# rev02_1.net
KiCad netlist of a schematic drawn in Altium Designer
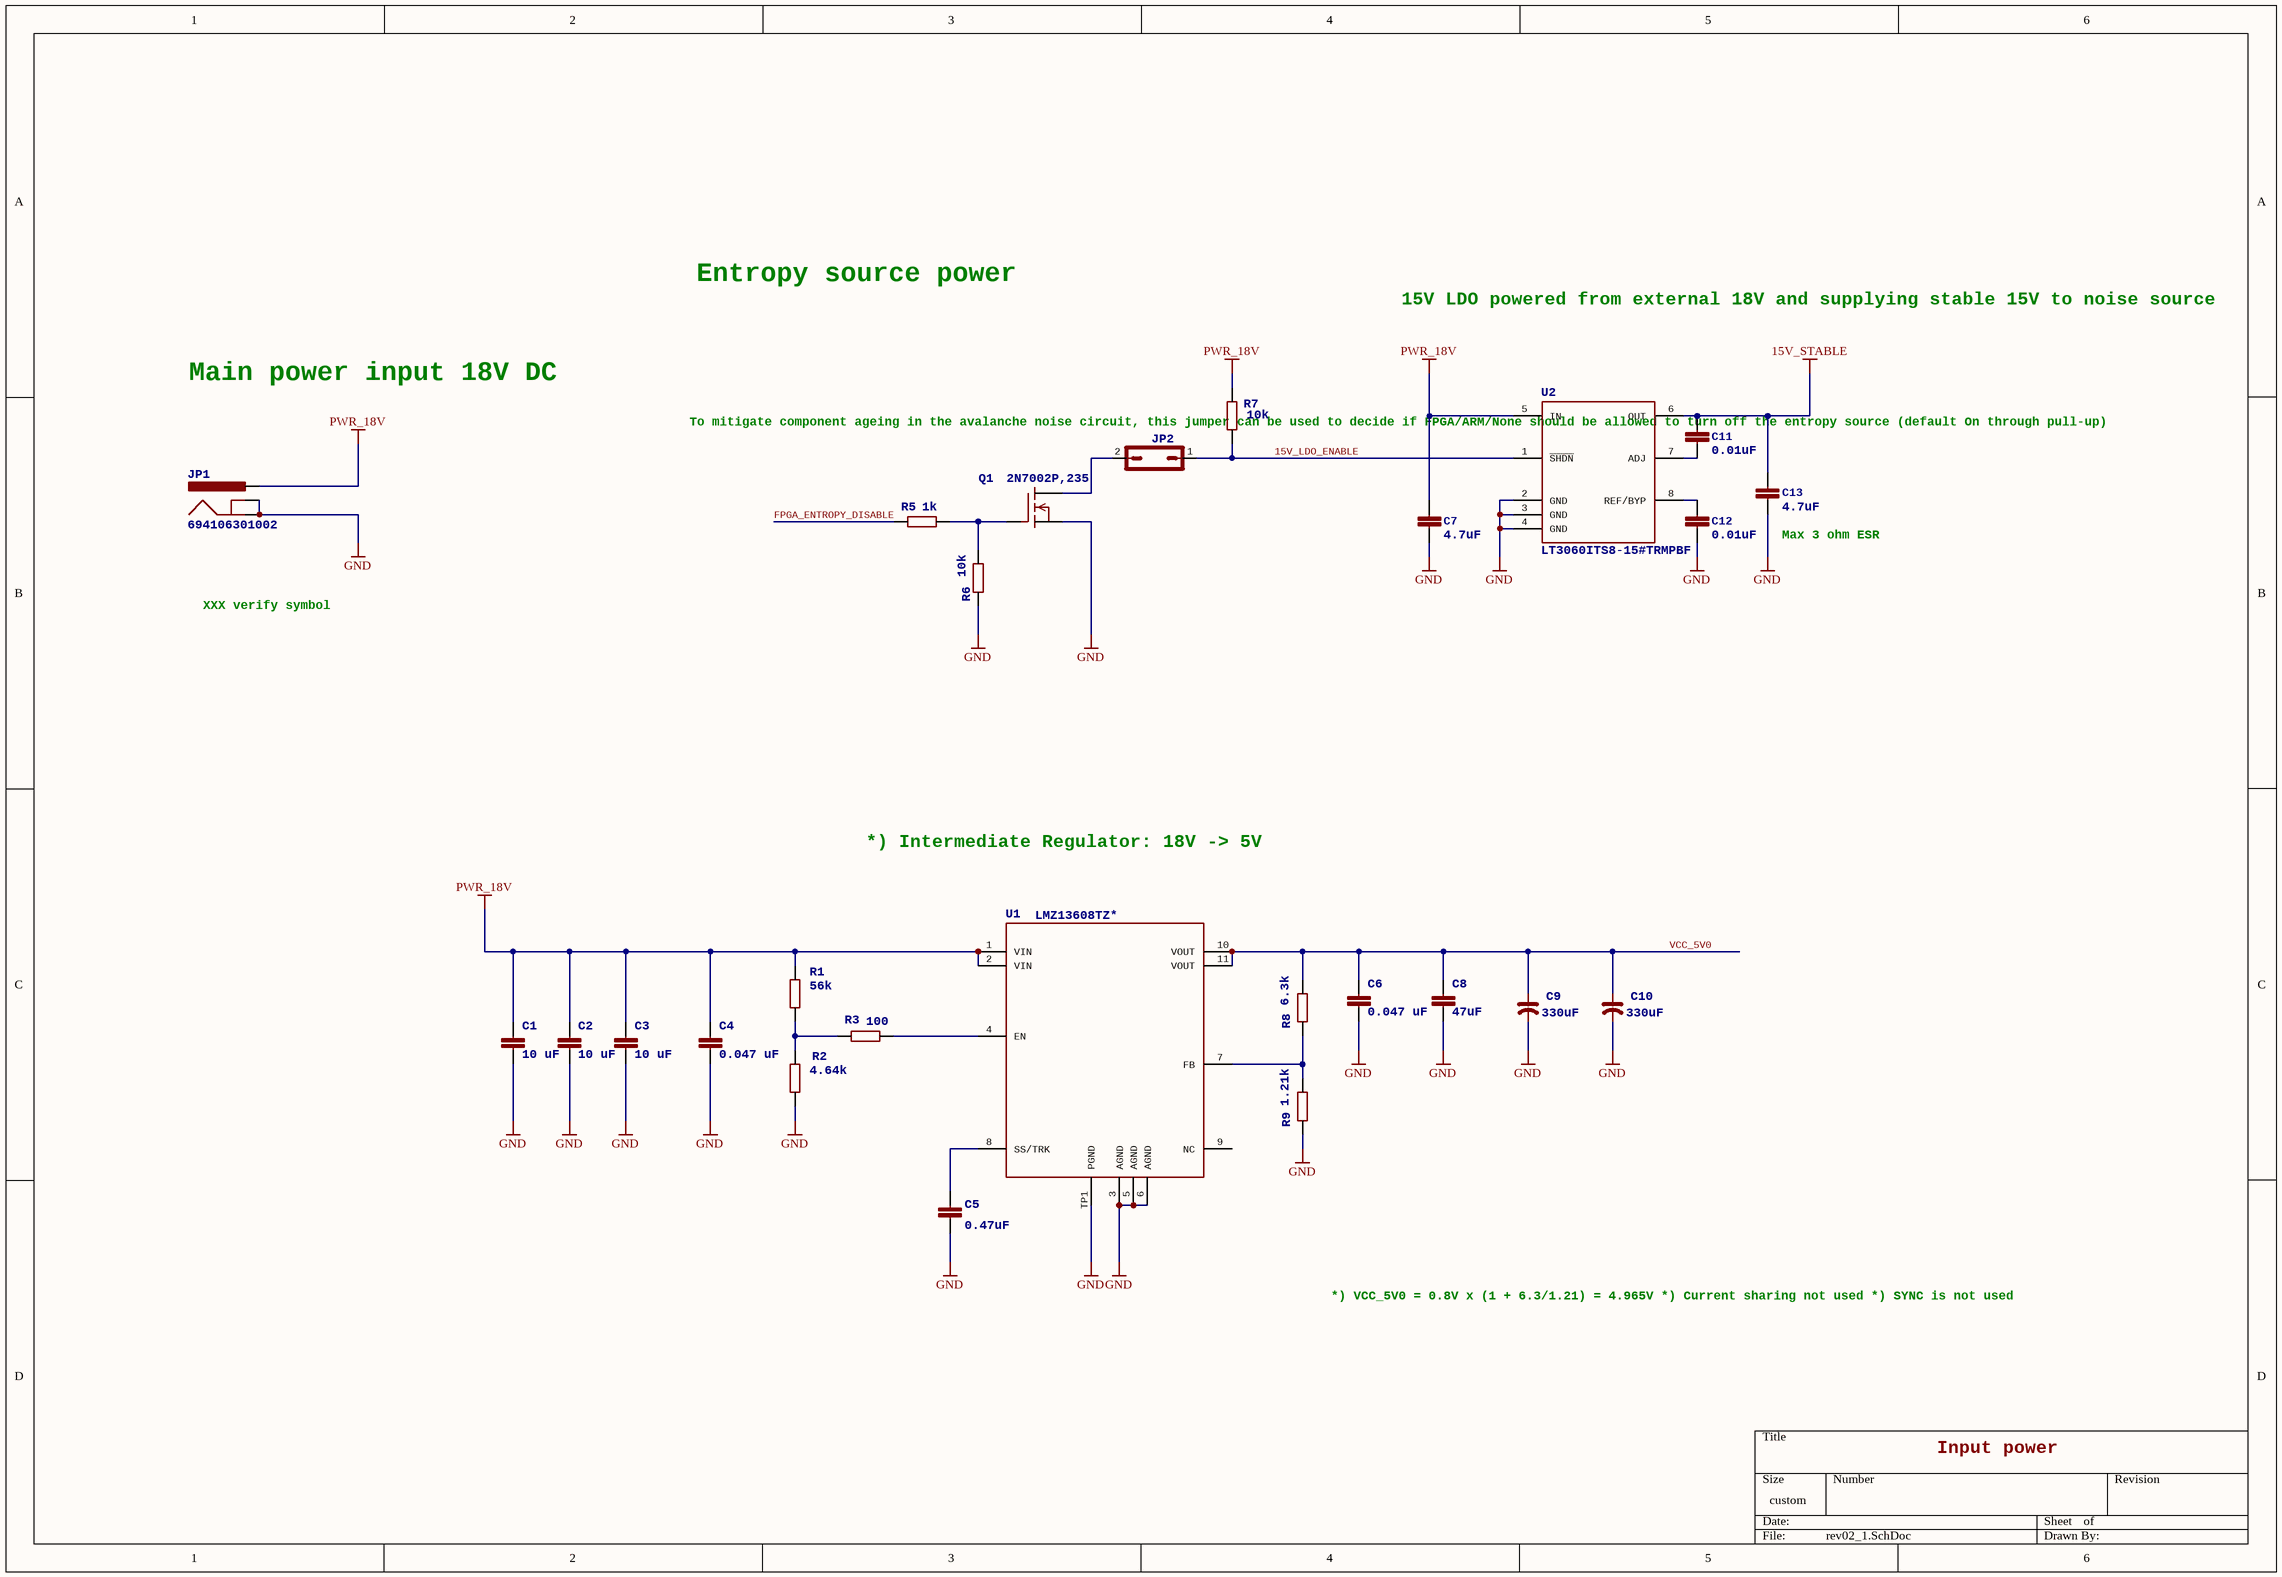
[diagram p0: rev02_1.SchDoc]

(export (version "E")
  (design (tool "Eeschema 10.0.6"))
  (components
    (comp (ref "C1")
      (value "10 uF")
      (footprint "C_1210")
      (description "1210 CAPACITOR")
      (fields (field (name "TOLERANCE") "10%") (field (name ">NAME") "C1"))
      (libsource (lib "resistor") (part "C-EUC1210"))
    )
    (comp (ref "C2")
      (value "10 uF")
      (footprint "C_1210")
      (description "1210 CAPACITOR")
      (fields (field (name "TOLERANCE") "10%") (field (name ">NAME") "C2"))
      (libsource (lib "resistor") (part "C-EUC1210"))
    )
    (comp (ref "C3")
      (value "10 uF")
      (footprint "C_1210")
      (description "1210 CAPACITOR")
      (fields (field (name "TOLERANCE") "10%") (field (name ">NAME") "C3"))
      (libsource (lib "resistor") (part "C-EUC1210"))
    )
    (comp (ref "C4")
      (value "0.047 uF")
      (footprint "C_0402")
      (description "0402 CAPACITOR")
      (fields (field (name "TOLERANCE") "10%") (field (name ">NAME") "C4"))
      (libsource (lib "resistor") (part "C-EUC0402"))
    )
    (comp (ref "C5")
      (value "0.47uF")
      (footprint "C_0402")
      (description "0402 CAPACITOR")
      (fields (field (name "TOLERANCE") "10%") (field (name "Comment") "GRM155R61A474KE15D"))
      (libsource (lib "resistor") (part "C-EUC0402"))
    )
    (comp (ref "C6")
      (value "0.047 uF")
      (footprint "C_0402")
      (description "0402 CAPACITOR")
      (fields (field (name "TOLERANCE") "10%") (field (name ">NAME") "C6"))
      (libsource (lib "resistor") (part "C-EUC0402"))
    )
    (comp (ref "C7")
      (value "4.7uF")
      (footprint "C_0805")
      (description "0805 CAPACITOR X7R 25V")
      (fields (field (name "Comment") "TMK212AB7475KG-T"))
      (libsource (lib "resistor") (part "C-EUC0603"))
    )
    (comp (ref "C8")
      (value "47uF")
      (footprint "C_1210")
      (description "1210 CAPACITOR X5R 6.3V")
      (fields
        (field (name "TOLERANCE") "20%")
        (field (name ">NAME") "C8")
        (field (name "Comment") "GRM32ER70J476ME20L")
      )
      (libsource (lib "resistor") (part "C-EUC1210"))
    )
    (comp (ref "C9")
      (value "330uF")
      (footprint "C_D")
      (description "Kemet Tantalum Capacitor")
      (fields (field (name "Comment") "T520D337M006ATE015"))
      (libsource (lib "rev02_1") (part "CP_E-035X080"))
    )
    (comp (ref "C10")
      (value "330uF")
      (footprint "C_D")
      (description "Kemet Tantalum Capacitor")
      (fields (field (name "Comment") "T520D337M006ATE015"))
      (libsource (lib "rev02_1") (part "CP_E-035X080"))
    )
    (comp (ref "C11")
      (value "0.01uF")
      (footprint "C_0402")
      (description "0402 CAPACITOR")
      (libsource (lib "rcl") (part "C-EUC0402"))
    )
    (comp (ref "C12")
      (value "0.01uF")
      (footprint "C_0402")
      (description "0402 CAPACITOR")
      (libsource (lib "rcl") (part "C-EUC0402"))
    )
    (comp (ref "C13")
      (value "4.7uF")
      (footprint "C_0805")
      (description "0805 CAPACITOR X7R 25V")
      (fields (field (name "Comment") "TMK212AB7475KG-T"))
      (libsource (lib "resistor") (part "C-EUC0603"))
    )
    (comp (ref "JP1")
      (value "694106301002")
      (footprint "694106301002")
      (description "Wurth Power Connector 5.5x2.1mm Barrel")
      (libsource (lib "rev02_1") (part "POWER_JACKSMD"))
    )
    (comp (ref "JP2")
      (value "61300211121")
      (footprint "PLS-2")
      (description "Wurth 2pins connector (for jumper)")
      (fields (field (name ">NAME") "JP2"))
      (libsource (lib "jumper") (part "JP1Q"))
    )
    (comp (ref "Q1")
      (value "2N7002P,235")
      (footprint "SOT-23")
      (description "OnSemi FET")
      (fields (field (name ">NAME") "Q1"))
      (libsource (lib "transistors_gaui") (part "2N7002"))
    )
    (comp (ref "R1")
      (value "56k")
      (footprint "R_0402")
      (description "0402 Resistor 1%")
      (libsource (lib "resistor") (part "R-EU_R0402"))
    )
    (comp (ref "R2")
      (value "4.64k")
      (footprint "R_0402")
      (description "0402 Resistor 1%")
      (libsource (lib "resistor") (part "R-EU_R0402"))
    )
    (comp (ref "R3")
      (value "100")
      (footprint "R_0402")
      (description "0402 Resistor 5%")
      (fields (field (name "TOLERANCE") "5%") (field (name ">NAME") "R3"))
      (libsource (lib "resistor") (part "R-EU_R0402"))
    )
    (comp (ref "R5")
      (value "1k")
      (footprint "R_0402")
      (description "0402 Resistor 5%")
      (libsource (lib "resistor") (part "R-EU_R0402"))
    )
    (comp (ref "R6")
      (value "10k")
      (footprint "R_0402")
      (description "0402 Resistor 5%")
      (fields (field (name "TOLERANCE") "5%") (field (name ">NAME") "R6"))
      (libsource (lib "resistor") (part "R-EU_R0402"))
    )
    (comp (ref "R7")
      (value "10k")
      (footprint "R_0402")
      (description "0402 Resistor 5%")
      (fields (field (name "TOLERANCE") "5%") (field (name ">NAME") "R7"))
      (libsource (lib "resistor") (part "R-EU_R0402"))
    )
    (comp (ref "R8")
      (value "6.3k")
      (footprint "R_0402")
      (description "0402 Resistor 1%")
      (libsource (lib "resistor") (part "R-EU_R0402"))
    )
    (comp (ref "R9")
      (value "1.21k")
      (footprint "R_0402")
      (description "0402 Resistor 1%")
      (libsource (lib "resistor") (part "R-EU_R0402"))
    )
    (comp (ref "U1")
      (value "LMZ13608TZ*")
      (footprint "NDY")
      (description "8-A SIMPLE SWITCHER® Power Module With 36-V Maximum Input Voltage")
      (fields (field (name "MPN") "LMZ13608TZ/NOPB"))
      (libsource (lib "rev02_1") (part "LMZ13608"))
    )
    (comp (ref "U2")
      (value "LT3060ITS8-15#TRMPBF")
      (footprint "TSOT-8-23")
      (description "Micropower, Low Noise, 100mA LDO, Linear Regulator")
      (libsource (lib "rev02_1") (part "LT3060ITS8-15"))
    )
  )
  (nets
    (net (code "1") (name "/15V_LDO_ENABLE") (class "Default")
      (node (ref "JP2") (pin "1") (pinfunction "1_1") (pintype "passive"))
      (node (ref "R7") (pin "2") (pinfunction "2_2") (pintype "passive"))
      (node (ref "U2") (pin "1") (pinfunction "~{SHDN}_1") (pintype "passive"))
    )
    (net (code "2") (name "/FPGA_ENTROPY_DISABLE") (class "Default")
      (node (ref "R5") (pin "1") (pinfunction "1_1") (pintype "passive"))
    )
    (net (code "3") (name "/VCC_5V0") (class "Default")
      (node (ref "C10") (pin "1") (pinfunction "+_1") (pintype "passive"))
      (node (ref "C6") (pin "1") (pinfunction "1_1") (pintype "passive"))
      (node (ref "C8") (pin "1") (pinfunction "1_1") (pintype "passive"))
      (node (ref "C9") (pin "1") (pinfunction "+_1") (pintype "passive"))
      (node (ref "R8") (pin "2") (pinfunction "2_2") (pintype "passive"))
      (node (ref "U1") (pin "10") (pinfunction "VOUT_10") (pintype "power_in"))
      (node (ref "U1") (pin "11") (pinfunction "VOUT_11") (pintype "power_in"))
    )
    (net (code "4") (name "15V_STABLE") (class "Default")
      (node (ref "C11") (pin "2") (pinfunction "2_2") (pintype "passive"))
      (node (ref "C13") (pin "1") (pinfunction "1_1") (pintype "passive"))
      (node (ref "U2") (pin "6") (pinfunction "OUT_6") (pintype "power_in"))
    )
    (net (code "5") (name "GND") (class "Default")
      (node (ref "C1") (pin "2") (pinfunction "2_2") (pintype "passive"))
      (node (ref "C10") (pin "2") (pinfunction "-_2") (pintype "passive"))
      (node (ref "C12") (pin "1") (pinfunction "1_1") (pintype "passive"))
      (node (ref "C13") (pin "2") (pinfunction "2_2") (pintype "passive"))
      (node (ref "C2") (pin "2") (pinfunction "2_2") (pintype "passive"))
      (node (ref "C3") (pin "2") (pinfunction "2_2") (pintype "passive"))
      (node (ref "C4") (pin "2") (pinfunction "2_2") (pintype "passive"))
      (node (ref "C5") (pin "2") (pinfunction "2_2") (pintype "passive"))
      (node (ref "C6") (pin "2") (pinfunction "2_2") (pintype "passive"))
      (node (ref "C7") (pin "2") (pinfunction "2_2") (pintype "passive"))
      (node (ref "C8") (pin "2") (pinfunction "2_2") (pintype "passive"))
      (node (ref "C9") (pin "2") (pinfunction "-_2") (pintype "passive"))
      (node (ref "JP1") (pin "2") (pinfunction "GND_2") (pintype "passive"))
      (node (ref "JP1") (pin "3") (pinfunction "GNDBREAK_3") (pintype "passive"))
      (node (ref "Q1") (pin "2") (pinfunction "S_2") (pintype "passive"))
      (node (ref "R2") (pin "1") (pinfunction "1_1") (pintype "passive"))
      (node (ref "R6") (pin "2") (pinfunction "2_2") (pintype "passive"))
      (node (ref "R9") (pin "1") (pinfunction "1_1") (pintype "passive"))
      (node (ref "U1") (pin "3") (pinfunction "AGND_3") (pintype "power_in"))
      (node (ref "U1") (pin "5") (pinfunction "AGND_5") (pintype "power_in"))
      (node (ref "U1") (pin "6") (pinfunction "AGND_6") (pintype "power_in"))
      (node (ref "U1") (pin "TP1") (pinfunction "PGND_TP1") (pintype "power_in"))
      (node (ref "U2") (pin "2") (pinfunction "GND_2") (pintype "power_in"))
      (node (ref "U2") (pin "3") (pinfunction "GND_3") (pintype "power_in"))
      (node (ref "U2") (pin "4") (pinfunction "GND_4") (pintype "power_in"))
    )
    (net (code "6") (name "Net-(Q1-D)") (class "Default")
      (node (ref "JP2") (pin "2") (pinfunction "2_2") (pintype "passive"))
      (node (ref "Q1") (pin "3") (pinfunction "D_3") (pintype "passive"))
    )
    (net (code "7") (name "Net-(Q1-G)") (class "Default")
      (node (ref "Q1") (pin "1") (pinfunction "G_1") (pintype "passive"))
      (node (ref "R5") (pin "2") (pinfunction "2_2") (pintype "passive"))
      (node (ref "R6") (pin "1") (pinfunction "1_1") (pintype "passive"))
    )
    (net (code "8") (name "Net-(R1-Pad1)") (class "Default")
      (node (ref "R1") (pin "1") (pinfunction "1_1") (pintype "passive"))
      (node (ref "R2") (pin "2") (pinfunction "2_2") (pintype "passive"))
      (node (ref "R3") (pin "1") (pinfunction "1_1") (pintype "passive"))
    )
    (net (code "9") (name "Net-(U1-EN)") (class "Default")
      (node (ref "R3") (pin "2") (pinfunction "2_2") (pintype "passive"))
      (node (ref "U1") (pin "4") (pinfunction "EN_4") (pintype "passive"))
    )
    (net (code "10") (name "Net-(U1-FB)") (class "Default")
      (node (ref "R8") (pin "1") (pinfunction "1_1") (pintype "passive"))
      (node (ref "R9") (pin "2") (pinfunction "2_2") (pintype "passive"))
      (node (ref "U1") (pin "7") (pinfunction "FB_7") (pintype "passive"))
    )
    (net (code "11") (name "Net-(U1-SS{slash}TRK)") (class "Default")
      (node (ref "C5") (pin "1") (pinfunction "1_1") (pintype "passive"))
      (node (ref "U1") (pin "8") (pinfunction "SS/TRK_8") (pintype "passive"))
    )
    (net (code "12") (name "Net-(U2-ADJ)") (class "Default")
      (node (ref "C11") (pin "1") (pinfunction "1_1") (pintype "passive"))
      (node (ref "U2") (pin "7") (pinfunction "ADJ_7") (pintype "passive"))
    )
    (net (code "13") (name "Net-(U2-REF{slash}BYP)") (class "Default")
      (node (ref "C12") (pin "2") (pinfunction "2_2") (pintype "passive"))
      (node (ref "U2") (pin "8") (pinfunction "REF/BYP_8") (pintype "passive"))
    )
    (net (code "14") (name "PWR_18V") (class "Default")
      (node (ref "C1") (pin "1") (pinfunction "1_1") (pintype "passive"))
      (node (ref "C2") (pin "1") (pinfunction "1_1") (pintype "passive"))
      (node (ref "C3") (pin "1") (pinfunction "1_1") (pintype "passive"))
      (node (ref "C4") (pin "1") (pinfunction "1_1") (pintype "passive"))
      (node (ref "C7") (pin "1") (pinfunction "1_1") (pintype "passive"))
      (node (ref "JP1") (pin "1") (pinfunction "PWR_1") (pintype "passive"))
      (node (ref "R1") (pin "2") (pinfunction "2_2") (pintype "passive"))
      (node (ref "R7") (pin "1") (pinfunction "1_1") (pintype "passive"))
      (node (ref "U1") (pin "1") (pinfunction "VIN_1") (pintype "power_in"))
      (node (ref "U1") (pin "2") (pinfunction "VIN_2") (pintype "power_in"))
      (node (ref "U2") (pin "5") (pinfunction "IN_5") (pintype "power_in"))
    )
    (net (code "15") (name "unconnected-(U1-NC-Pad9)") (class "Default")
      (node (ref "U1") (pin "9") (pinfunction "NC_9") (pintype "passive"))
    )
  )
)
